# SPI_MUX.net
KiCad netlist of a schematic drawn in Altium Designer
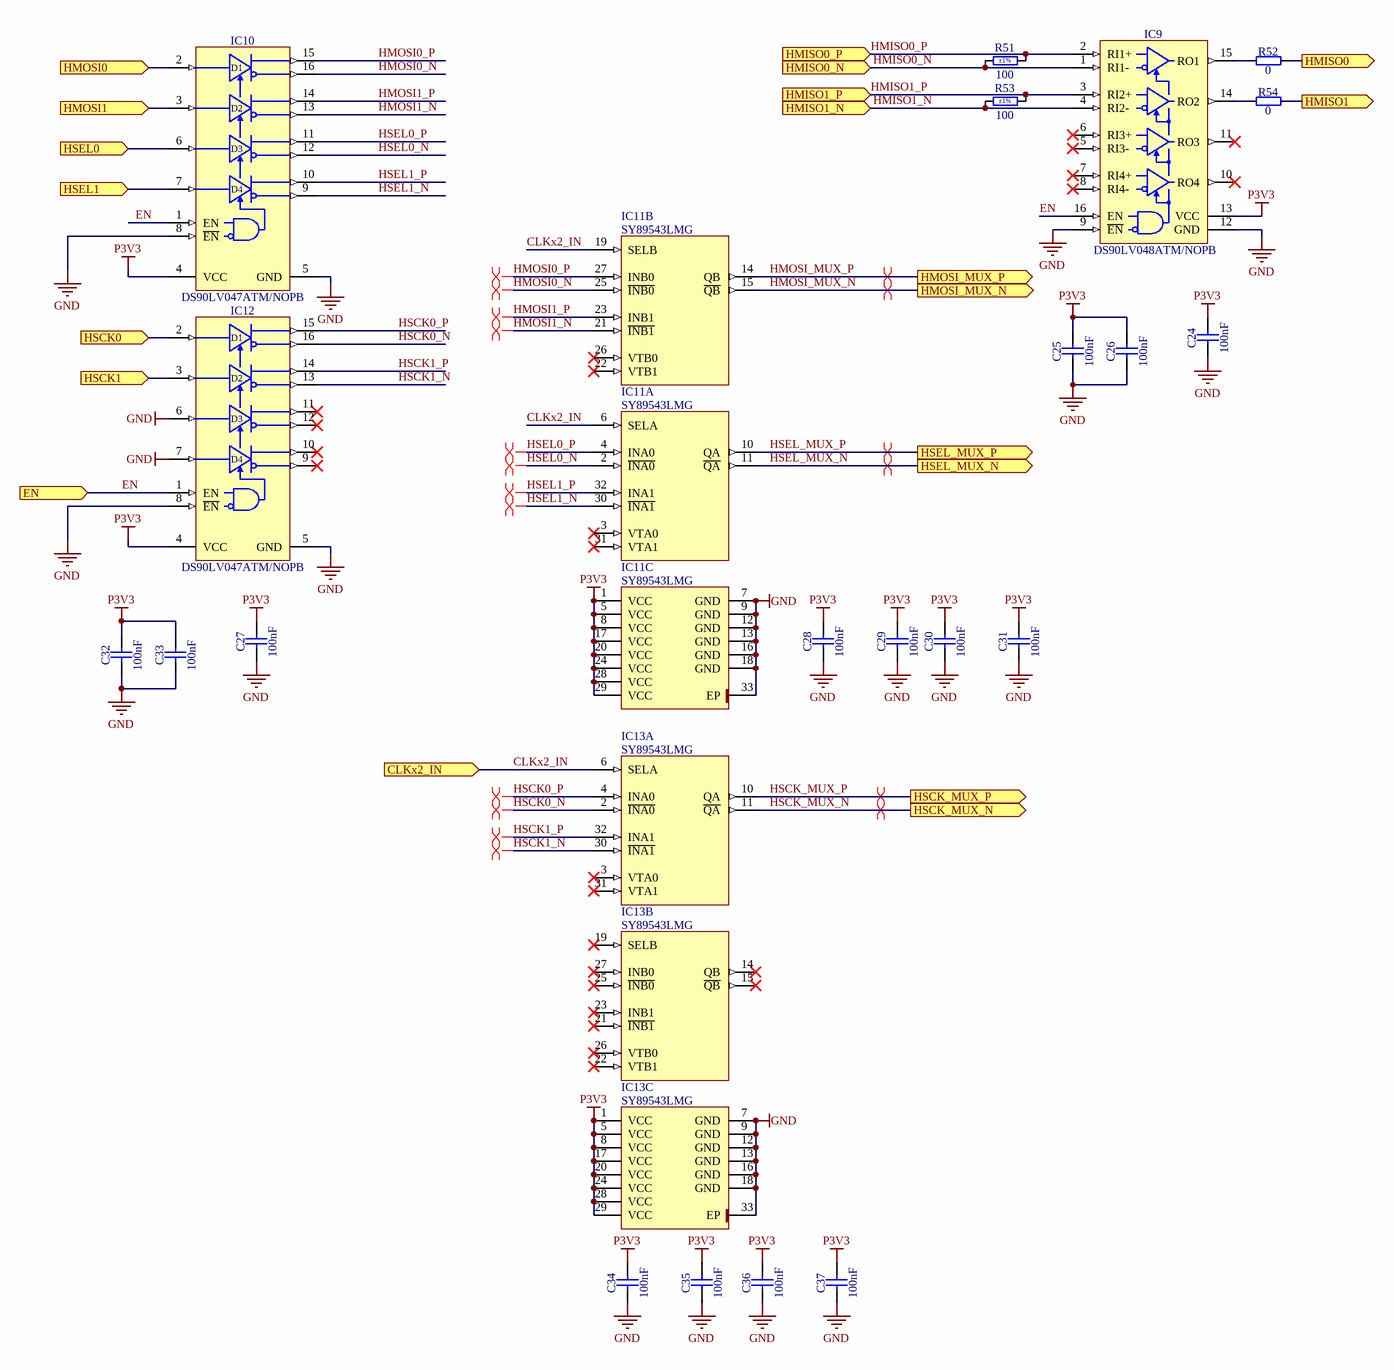
[diagram p0: SPI_MUX.SchDoc]

(export (version "E")
  (design (tool "Eeschema 10.0.6"))
  (components
    (comp (ref "C24")
      (value "100nF")
      (footprint "CAPC1005X55N")
      (description "Non-polarised capacitor")
      (fields
        (field (name "PART NUMBER") "CC0402_100NF_50V_10%_X7R")
        (field (name "VOLTAGE") "50V")
        (field (name "AUTHOR") "CERN DEM MR")
      )
      (libsource (lib "Capacitors") (part "Capacitor - non polarized"))
    )
    (comp (ref "C25")
      (value "100nF")
      (footprint "CAPC1005X55N")
      (description "Non-polarised capacitor")
      (fields
        (field (name "PART NUMBER") "CC0402_100NF_50V_10%_X7R")
        (field (name "VOLTAGE") "50V")
        (field (name "AUTHOR") "CERN DEM MR")
      )
      (libsource (lib "Capacitors") (part "Capacitor - non polarized"))
    )
    (comp (ref "C26")
      (value "100nF")
      (footprint "CAPC1005X55N")
      (description "Non-polarised capacitor")
      (fields
        (field (name "PART NUMBER") "CC0402_100NF_50V_10%_X7R")
        (field (name "VOLTAGE") "50V")
        (field (name "AUTHOR") "CERN DEM MR")
      )
      (libsource (lib "Capacitors") (part "Capacitor - non polarized"))
    )
    (comp (ref "C27")
      (value "100nF")
      (footprint "CAPC1005X55N")
      (description "Non-polarised capacitor")
      (fields
        (field (name "PART NUMBER") "CC0402_100NF_50V_10%_X7R")
        (field (name "VOLTAGE") "50V")
        (field (name "AUTHOR") "CERN DEM MR")
      )
      (libsource (lib "Capacitors") (part "Capacitor - non polarized"))
    )
    (comp (ref "C28")
      (value "100nF")
      (footprint "CAPC1005X55N")
      (description "Non-polarised capacitor")
      (fields
        (field (name "PART NUMBER") "CC0402_100NF_50V_10%_X7R")
        (field (name "VOLTAGE") "50V")
        (field (name "AUTHOR") "CERN DEM MR")
      )
      (libsource (lib "Capacitors") (part "Capacitor - non polarized"))
    )
    (comp (ref "C29")
      (value "100nF")
      (footprint "CAPC1005X55N")
      (description "Non-polarised capacitor")
      (fields
        (field (name "PART NUMBER") "CC0402_100NF_50V_10%_X7R")
        (field (name "VOLTAGE") "50V")
        (field (name "AUTHOR") "CERN DEM MR")
      )
      (libsource (lib "Capacitors") (part "Capacitor - non polarized"))
    )
    (comp (ref "C30")
      (value "100nF")
      (footprint "CAPC1005X55N")
      (description "Non-polarised capacitor")
      (fields
        (field (name "PART NUMBER") "CC0402_100NF_50V_10%_X7R")
        (field (name "VOLTAGE") "50V")
        (field (name "AUTHOR") "CERN DEM MR")
      )
      (libsource (lib "Capacitors") (part "Capacitor - non polarized"))
    )
    (comp (ref "C31")
      (value "100nF")
      (footprint "CAPC1005X55N")
      (description "Non-polarised capacitor")
      (fields
        (field (name "PART NUMBER") "CC0402_100NF_50V_10%_X7R")
        (field (name "VOLTAGE") "50V")
        (field (name "AUTHOR") "CERN DEM MR")
      )
      (libsource (lib "Capacitors") (part "Capacitor - non polarized"))
    )
    (comp (ref "C32")
      (value "100nF")
      (footprint "CAPC1005X55N")
      (description "Non-polarised capacitor")
      (fields
        (field (name "PART NUMBER") "CC0402_100NF_50V_10%_X7R")
        (field (name "VOLTAGE") "50V")
        (field (name "AUTHOR") "CERN DEM MR")
      )
      (libsource (lib "Capacitors") (part "Capacitor - non polarized"))
    )
    (comp (ref "C33")
      (value "100nF")
      (footprint "CAPC1005X55N")
      (description "Non-polarised capacitor")
      (fields
        (field (name "PART NUMBER") "CC0402_100NF_50V_10%_X7R")
        (field (name "VOLTAGE") "50V")
        (field (name "AUTHOR") "CERN DEM MR")
      )
      (libsource (lib "Capacitors") (part "Capacitor - non polarized"))
    )
    (comp (ref "C34")
      (value "100nF")
      (footprint "CAPC1005X55N")
      (description "Non-polarised capacitor")
      (fields
        (field (name "PART NUMBER") "CC0402_100NF_50V_10%_X7R")
        (field (name "VOLTAGE") "50V")
        (field (name "AUTHOR") "CERN DEM MR")
      )
      (libsource (lib "Capacitors") (part "Capacitor - non polarized"))
    )
    (comp (ref "C35")
      (value "100nF")
      (footprint "CAPC1005X55N")
      (description "Non-polarised capacitor")
      (fields
        (field (name "PART NUMBER") "CC0402_100NF_50V_10%_X7R")
        (field (name "VOLTAGE") "50V")
        (field (name "AUTHOR") "CERN DEM MR")
      )
      (libsource (lib "Capacitors") (part "Capacitor - non polarized"))
    )
    (comp (ref "C36")
      (value "100nF")
      (footprint "CAPC1005X55N")
      (description "Non-polarised capacitor")
      (fields
        (field (name "PART NUMBER") "CC0402_100NF_50V_10%_X7R")
        (field (name "VOLTAGE") "50V")
        (field (name "AUTHOR") "CERN DEM MR")
      )
      (libsource (lib "Capacitors") (part "Capacitor - non polarized"))
    )
    (comp (ref "C37")
      (value "100nF")
      (footprint "CAPC1005X55N")
      (description "Non-polarised capacitor")
      (fields
        (field (name "PART NUMBER") "CC0402_100NF_50V_10%_X7R")
        (field (name "VOLTAGE") "50V")
        (field (name "AUTHOR") "CERN DEM MR")
      )
      (libsource (lib "Capacitors") (part "Capacitor - non polarized"))
    )
    (comp (ref "IC9")
      (value "DS90LV048ATM/NOPB")
      (footprint "SOIC127P600X175-16N")
      (description "3V LVDS Quad CMOS Differential Line Receiver")
      (fields
        (field (name "MANUFACTURER") "TEXAS INSTRUMENTS")
        (field (name "MANUFACTURER PART NUMBER") "DS90LV048ATM")
        (field (name "AUTHOR") "CERN DEM JLC")
      )
      (libsource (lib "ICs And Semiconductors") (part "DS90LV048A"))
    )
    (comp (ref "IC10")
      (value "DS90LV047ATM/NOPB")
      (footprint "SOIC127P600X175-16N")
      (description "3V LVDS Quad CMOS Differential Line Driver")
      (fields
        (field (name "MANUFACTURER") "TEXAS INSTRUMENTS")
        (field (name "MANUFACTURER PART NUMBER") "DS90LV047ATM")
        (field (name "AUTHOR") "CERN DEM JLC")
      )
      (libsource (lib "ICs And Semiconductors") (part "DS90LV047A"))
    )
    (comp (ref "IC11")
      (value "SY89543LMG")
      (footprint "QFN50P500X500X90-33N-S320")
      (description "3.3V, 3.2Gbps Dual, Differential 2:1 LVDS Multiplexer With Internal Termination")
      (fields (field (name "MANUFACTURER") "MICREL") (field (name "AUTHOR") "CERN DEM JLC"))
      (libsource (lib "ICs And Semiconductors") (part "SY89543L"))
    )
    (comp (ref "IC12")
      (value "DS90LV047ATM/NOPB")
      (footprint "SOIC127P600X175-16N")
      (description "3V LVDS Quad CMOS Differential Line Driver")
      (fields
        (field (name "MANUFACTURER") "TEXAS INSTRUMENTS")
        (field (name "MANUFACTURER PART NUMBER") "DS90LV047ATM")
        (field (name "AUTHOR") "CERN DEM JLC")
      )
      (libsource (lib "ICs And Semiconductors") (part "DS90LV047A"))
    )
    (comp (ref "IC13")
      (value "SY89543LMG")
      (footprint "QFN50P500X500X90-33N-S320")
      (description "3.3V, 3.2Gbps Dual, Differential 2:1 LVDS Multiplexer With Internal Termination")
      (fields (field (name "MANUFACTURER") "MICREL") (field (name "AUTHOR") "CERN DEM JLC"))
      (libsource (lib "ICs And Semiconductors") (part "SY89543L"))
    )
    (comp (ref "R51")
      (value "100")
      (footprint "RESC1005X40N")
      (description "Resistor - 1%")
      (fields
        (field (name "TOLERANCE") "±1%")
        (field (name "PART NUMBER") "R0402_100R_1%_0.0625W_100PPM")
        (field (name "POWER") "0.0625W")
        (field (name "AUTHOR") "CERN DEM JLC")
      )
      (libsource (lib "Resistors") (part "Resistor - 1%"))
    )
    (comp (ref "R52")
      (value "0")
      (footprint "RESC1005X40N")
      (description "Resistor")
      (fields
        (field (name "PART NUMBER") "R0402_0R_JUMPER")
        (field (name "MANUFACTURER") "GENERIC")
        (field (name "AUTHOR") "CERN DEM JLC")
      )
      (libsource (lib "Resistors") (part "Resistor"))
    )
    (comp (ref "R53")
      (value "100")
      (footprint "RESC1005X40N")
      (description "Resistor - 1%")
      (fields
        (field (name "TOLERANCE") "±1%")
        (field (name "PART NUMBER") "R0402_100R_1%_0.0625W_100PPM")
        (field (name "POWER") "0.0625W")
        (field (name "AUTHOR") "CERN DEM JLC")
      )
      (libsource (lib "Resistors") (part "Resistor - 1%"))
    )
    (comp (ref "R54")
      (value "0")
      (footprint "RESC1005X40N")
      (description "Resistor")
      (fields
        (field (name "PART NUMBER") "R0402_0R_JUMPER")
        (field (name "MANUFACTURER") "GENERIC")
        (field (name "AUTHOR") "CERN DEM JLC")
      )
      (libsource (lib "Resistors") (part "Resistor"))
    )
  )
  (nets
    (net (code "1") (name "/CLKx2_IN") (class "Default")
      (node (ref "IC11") (pin "19") (pinfunction "SELB_19") (pintype "input"))
      (node (ref "IC11") (pin "6") (pinfunction "SELA_6") (pintype "input"))
      (node (ref "IC13") (pin "6") (pinfunction "SELA_6") (pintype "input"))
    )
    (net (code "2") (name "/EN") (class "Default")
      (node (ref "IC10") (pin "1") (pinfunction "EN_1") (pintype "input"))
      (node (ref "IC12") (pin "1") (pinfunction "EN_1") (pintype "input"))
      (node (ref "IC9") (pin "16") (pinfunction "EN_16") (pintype "input"))
    )
    (net (code "3") (name "/HMISO0") (class "Default")
      (node (ref "R52") (pin "2") (pinfunction "2_2") (pintype "passive"))
    )
    (net (code "4") (name "/HMISO0_N") (class "Default")
      (node (ref "IC9") (pin "1") (pinfunction "RI1-_1") (pintype "input"))
      (node (ref "R51") (pin "1") (pinfunction "1_1") (pintype "passive"))
    )
    (net (code "5") (name "/HMISO0_P") (class "Default")
      (node (ref "IC9") (pin "2") (pinfunction "RI1+_2") (pintype "input"))
      (node (ref "R51") (pin "2") (pinfunction "2_2") (pintype "passive"))
    )
    (net (code "6") (name "/HMISO1") (class "Default")
      (node (ref "R54") (pin "2") (pinfunction "2_2") (pintype "passive"))
    )
    (net (code "7") (name "/HMISO1_N") (class "Default")
      (node (ref "IC9") (pin "4") (pinfunction "RI2-_4") (pintype "input"))
      (node (ref "R53") (pin "1") (pinfunction "1_1") (pintype "passive"))
    )
    (net (code "8") (name "/HMISO1_P") (class "Default")
      (node (ref "IC9") (pin "3") (pinfunction "RI2+_3") (pintype "input"))
      (node (ref "R53") (pin "2") (pinfunction "2_2") (pintype "passive"))
    )
    (net (code "9") (name "/HMOSI0") (class "Default")
      (node (ref "IC10") (pin "2") (pinfunction "DIN1_2") (pintype "input"))
    )
    (net (code "10") (name "/HMOSI0_N") (class "Default")
      (node (ref "IC10") (pin "16") (pinfunction "DOUT1-_16") (pintype "output"))
      (node (ref "IC11") (pin "25") (pinfunction "~{INB0}_25") (pintype "input"))
    )
    (net (code "11") (name "/HMOSI0_P") (class "Default")
      (node (ref "IC10") (pin "15") (pinfunction "DOUT1+_15") (pintype "output"))
      (node (ref "IC11") (pin "27") (pinfunction "INB0_27") (pintype "input"))
    )
    (net (code "12") (name "/HMOSI1") (class "Default")
      (node (ref "IC10") (pin "3") (pinfunction "DIN2_3") (pintype "input"))
    )
    (net (code "13") (name "/HMOSI1_N") (class "Default")
      (node (ref "IC10") (pin "13") (pinfunction "DOUT2-_13") (pintype "output"))
      (node (ref "IC11") (pin "21") (pinfunction "~{INB1}_21") (pintype "input"))
    )
    (net (code "14") (name "/HMOSI1_P") (class "Default")
      (node (ref "IC10") (pin "14") (pinfunction "DOUT2+_14") (pintype "output"))
      (node (ref "IC11") (pin "23") (pinfunction "INB1_23") (pintype "input"))
    )
    (net (code "15") (name "/HMOSI_MUX_N") (class "Default")
      (node (ref "IC11") (pin "15") (pinfunction "~{QB}_15") (pintype "output"))
    )
    (net (code "16") (name "/HMOSI_MUX_P") (class "Default")
      (node (ref "IC11") (pin "14") (pinfunction "QB_14") (pintype "output"))
    )
    (net (code "17") (name "/HSCK0") (class "Default")
      (node (ref "IC12") (pin "2") (pinfunction "DIN1_2") (pintype "input"))
    )
    (net (code "18") (name "/HSCK0_N") (class "Default")
      (node (ref "IC12") (pin "16") (pinfunction "DOUT1-_16") (pintype "output"))
      (node (ref "IC13") (pin "2") (pinfunction "~{INA0}_2") (pintype "input"))
    )
    (net (code "19") (name "/HSCK0_P") (class "Default")
      (node (ref "IC12") (pin "15") (pinfunction "DOUT1+_15") (pintype "output"))
      (node (ref "IC13") (pin "4") (pinfunction "INA0_4") (pintype "input"))
    )
    (net (code "20") (name "/HSCK1") (class "Default")
      (node (ref "IC12") (pin "3") (pinfunction "DIN2_3") (pintype "input"))
    )
    (net (code "21") (name "/HSCK1_N") (class "Default")
      (node (ref "IC12") (pin "13") (pinfunction "DOUT2-_13") (pintype "output"))
      (node (ref "IC13") (pin "30") (pinfunction "~{INA1}_30") (pintype "input"))
    )
    (net (code "22") (name "/HSCK1_P") (class "Default")
      (node (ref "IC12") (pin "14") (pinfunction "DOUT2+_14") (pintype "output"))
      (node (ref "IC13") (pin "32") (pinfunction "INA1_32") (pintype "input"))
    )
    (net (code "23") (name "/HSCK_MUX_N") (class "Default")
      (node (ref "IC13") (pin "11") (pinfunction "~{QA}_11") (pintype "output"))
    )
    (net (code "24") (name "/HSCK_MUX_P") (class "Default")
      (node (ref "IC13") (pin "10") (pinfunction "QA_10") (pintype "output"))
    )
    (net (code "25") (name "/HSEL0") (class "Default")
      (node (ref "IC10") (pin "6") (pinfunction "DIN3_6") (pintype "input"))
    )
    (net (code "26") (name "/HSEL0_N") (class "Default")
      (node (ref "IC10") (pin "12") (pinfunction "DOUT3-_12") (pintype "output"))
      (node (ref "IC11") (pin "2") (pinfunction "~{INA0}_2") (pintype "input"))
    )
    (net (code "27") (name "/HSEL0_P") (class "Default")
      (node (ref "IC10") (pin "11") (pinfunction "DOUT3+_11") (pintype "output"))
      (node (ref "IC11") (pin "4") (pinfunction "INA0_4") (pintype "input"))
    )
    (net (code "28") (name "/HSEL1") (class "Default")
      (node (ref "IC10") (pin "7") (pinfunction "DIN4_7") (pintype "input"))
    )
    (net (code "29") (name "/HSEL1_N") (class "Default")
      (node (ref "IC10") (pin "9") (pinfunction "DOUT4-_9") (pintype "output"))
      (node (ref "IC11") (pin "30") (pinfunction "~{INA1}_30") (pintype "input"))
    )
    (net (code "30") (name "/HSEL1_P") (class "Default")
      (node (ref "IC10") (pin "10") (pinfunction "DOUT4+_10") (pintype "output"))
      (node (ref "IC11") (pin "32") (pinfunction "INA1_32") (pintype "input"))
    )
    (net (code "31") (name "/HSEL_MUX_N") (class "Default")
      (node (ref "IC11") (pin "11") (pinfunction "~{QA}_11") (pintype "output"))
    )
    (net (code "32") (name "/HSEL_MUX_P") (class "Default")
      (node (ref "IC11") (pin "10") (pinfunction "QA_10") (pintype "output"))
    )
    (net (code "33") (name "GND") (class "Default")
      (node (ref "C24") (pin "1") (pinfunction "1_1") (pintype "passive"))
      (node (ref "C25") (pin "1") (pinfunction "1_1") (pintype "passive"))
      (node (ref "C26") (pin "1") (pinfunction "1_1") (pintype "passive"))
      (node (ref "C27") (pin "1") (pinfunction "1_1") (pintype "passive"))
      (node (ref "C28") (pin "1") (pinfunction "1_1") (pintype "passive"))
      (node (ref "C29") (pin "1") (pinfunction "1_1") (pintype "passive"))
      (node (ref "C30") (pin "1") (pinfunction "1_1") (pintype "passive"))
      (node (ref "C31") (pin "1") (pinfunction "1_1") (pintype "passive"))
      (node (ref "C32") (pin "1") (pinfunction "1_1") (pintype "passive"))
      (node (ref "C33") (pin "1") (pinfunction "1_1") (pintype "passive"))
      (node (ref "C34") (pin "1") (pinfunction "1_1") (pintype "passive"))
      (node (ref "C35") (pin "1") (pinfunction "1_1") (pintype "passive"))
      (node (ref "C36") (pin "1") (pinfunction "1_1") (pintype "passive"))
      (node (ref "C37") (pin "1") (pinfunction "1_1") (pintype "passive"))
      (node (ref "IC10") (pin "5") (pinfunction "GND_5") (pintype "power_in"))
      (node (ref "IC10") (pin "8") (pinfunction "~{EN}_8") (pintype "input"))
      (node (ref "IC11") (pin "12") (pinfunction "GND_12") (pintype "power_in"))
      (node (ref "IC11") (pin "13") (pinfunction "GND_13") (pintype "power_in"))
      (node (ref "IC11") (pin "16") (pinfunction "GND_16") (pintype "power_in"))
      (node (ref "IC11") (pin "18") (pinfunction "GND_18") (pintype "power_in"))
      (node (ref "IC11") (pin "33") (pinfunction "EP_33") (pintype "power_in"))
      (node (ref "IC11") (pin "7") (pinfunction "GND_7") (pintype "power_in"))
      (node (ref "IC11") (pin "9") (pinfunction "GND_9") (pintype "power_in"))
      (node (ref "IC12") (pin "5") (pinfunction "GND_5") (pintype "power_in"))
      (node (ref "IC12") (pin "6") (pinfunction "DIN3_6") (pintype "input"))
      (node (ref "IC12") (pin "7") (pinfunction "DIN4_7") (pintype "input"))
      (node (ref "IC12") (pin "8") (pinfunction "~{EN}_8") (pintype "input"))
      (node (ref "IC13") (pin "12") (pinfunction "GND_12") (pintype "power_in"))
      (node (ref "IC13") (pin "13") (pinfunction "GND_13") (pintype "power_in"))
      (node (ref "IC13") (pin "16") (pinfunction "GND_16") (pintype "power_in"))
      (node (ref "IC13") (pin "18") (pinfunction "GND_18") (pintype "power_in"))
      (node (ref "IC13") (pin "33") (pinfunction "EP_33") (pintype "power_in"))
      (node (ref "IC13") (pin "7") (pinfunction "GND_7") (pintype "power_in"))
      (node (ref "IC13") (pin "9") (pinfunction "GND_9") (pintype "power_in"))
      (node (ref "IC9") (pin "12") (pinfunction "GND_12") (pintype "power_in"))
      (node (ref "IC9") (pin "9") (pinfunction "~{EN}_9") (pintype "input"))
    )
    (net (code "34") (name "Net-(IC9-RO1)") (class "Default")
      (node (ref "IC9") (pin "15") (pinfunction "RO1_15") (pintype "output"))
      (node (ref "R52") (pin "1") (pinfunction "1_1") (pintype "passive"))
    )
    (net (code "35") (name "Net-(IC9-RO2)") (class "Default")
      (node (ref "IC9") (pin "14") (pinfunction "RO2_14") (pintype "output"))
      (node (ref "R54") (pin "1") (pinfunction "1_1") (pintype "passive"))
    )
    (net (code "36") (name "P3V3") (class "Default")
      (node (ref "C24") (pin "2") (pinfunction "2_2") (pintype "passive"))
      (node (ref "C25") (pin "2") (pinfunction "2_2") (pintype "passive"))
      (node (ref "C26") (pin "2") (pinfunction "2_2") (pintype "passive"))
      (node (ref "C27") (pin "2") (pinfunction "2_2") (pintype "passive"))
      (node (ref "C28") (pin "2") (pinfunction "2_2") (pintype "passive"))
      (node (ref "C29") (pin "2") (pinfunction "2_2") (pintype "passive"))
      (node (ref "C30") (pin "2") (pinfunction "2_2") (pintype "passive"))
      (node (ref "C31") (pin "2") (pinfunction "2_2") (pintype "passive"))
      (node (ref "C32") (pin "2") (pinfunction "2_2") (pintype "passive"))
      (node (ref "C33") (pin "2") (pinfunction "2_2") (pintype "passive"))
      (node (ref "C34") (pin "2") (pinfunction "2_2") (pintype "passive"))
      (node (ref "C35") (pin "2") (pinfunction "2_2") (pintype "passive"))
      (node (ref "C36") (pin "2") (pinfunction "2_2") (pintype "passive"))
      (node (ref "C37") (pin "2") (pinfunction "2_2") (pintype "passive"))
      (node (ref "IC10") (pin "4") (pinfunction "VCC_4") (pintype "power_in"))
      (node (ref "IC11") (pin "1") (pinfunction "VCC_1") (pintype "power_in"))
      (node (ref "IC11") (pin "17") (pinfunction "VCC_17") (pintype "power_in"))
      (node (ref "IC11") (pin "20") (pinfunction "VCC_20") (pintype "power_in"))
      (node (ref "IC11") (pin "24") (pinfunction "VCC_24") (pintype "power_in"))
      (node (ref "IC11") (pin "28") (pinfunction "VCC_28") (pintype "power_in"))
      (node (ref "IC11") (pin "29") (pinfunction "VCC_29") (pintype "power_in"))
      (node (ref "IC11") (pin "5") (pinfunction "VCC_5") (pintype "power_in"))
      (node (ref "IC11") (pin "8") (pinfunction "VCC_8") (pintype "power_in"))
      (node (ref "IC12") (pin "4") (pinfunction "VCC_4") (pintype "power_in"))
      (node (ref "IC13") (pin "1") (pinfunction "VCC_1") (pintype "power_in"))
      (node (ref "IC13") (pin "17") (pinfunction "VCC_17") (pintype "power_in"))
      (node (ref "IC13") (pin "20") (pinfunction "VCC_20") (pintype "power_in"))
      (node (ref "IC13") (pin "24") (pinfunction "VCC_24") (pintype "power_in"))
      (node (ref "IC13") (pin "28") (pinfunction "VCC_28") (pintype "power_in"))
      (node (ref "IC13") (pin "29") (pinfunction "VCC_29") (pintype "power_in"))
      (node (ref "IC13") (pin "5") (pinfunction "VCC_5") (pintype "power_in"))
      (node (ref "IC13") (pin "8") (pinfunction "VCC_8") (pintype "power_in"))
      (node (ref "IC9") (pin "13") (pinfunction "VCC_13") (pintype "power_in"))
    )
    (net (code "37") (name "unconnected-(IC9-RI3+-Pad6)") (class "Default")
      (node (ref "IC9") (pin "6") (pinfunction "RI3+_6") (pintype "input+no_connect"))
    )
    (net (code "38") (name "unconnected-(IC9-RI3--Pad5)") (class "Default")
      (node (ref "IC9") (pin "5") (pinfunction "RI3-_5") (pintype "input+no_connect"))
    )
    (net (code "39") (name "unconnected-(IC9-RI4+-Pad7)") (class "Default")
      (node (ref "IC9") (pin "7") (pinfunction "RI4+_7") (pintype "input+no_connect"))
    )
    (net (code "40") (name "unconnected-(IC9-RI4--Pad8)") (class "Default")
      (node (ref "IC9") (pin "8") (pinfunction "RI4-_8") (pintype "input+no_connect"))
    )
    (net (code "41") (name "unconnected-(IC9-RO3-Pad11)") (class "Default")
      (node (ref "IC9") (pin "11") (pinfunction "RO3_11") (pintype "output+no_connect"))
    )
    (net (code "42") (name "unconnected-(IC9-RO4-Pad10)") (class "Default")
      (node (ref "IC9") (pin "10") (pinfunction "RO4_10") (pintype "output+no_connect"))
    )
    (net (code "43") (name "unconnected-(IC11A-VTA0-Pad3)") (class "Default")
      (node (ref "IC11") (pin "3") (pinfunction "VTA0_3") (pintype "input+no_connect"))
    )
    (net (code "44") (name "unconnected-(IC11A-VTA1-Pad31)") (class "Default")
      (node (ref "IC11") (pin "31") (pinfunction "VTA1_31") (pintype "input+no_connect"))
    )
    (net (code "45") (name "unconnected-(IC11B-VTB0-Pad26)") (class "Default")
      (node (ref "IC11") (pin "26") (pinfunction "VTB0_26") (pintype "input+no_connect"))
    )
    (net (code "46") (name "unconnected-(IC11B-VTB1-Pad22)") (class "Default")
      (node (ref "IC11") (pin "22") (pinfunction "VTB1_22") (pintype "input+no_connect"))
    )
    (net (code "47") (name "unconnected-(IC12-DOUT3+-Pad11)") (class "Default")
      (node (ref "IC12") (pin "11") (pinfunction "DOUT3+_11") (pintype "output+no_connect"))
    )
    (net (code "48") (name "unconnected-(IC12-DOUT3--Pad12)") (class "Default")
      (node (ref "IC12") (pin "12") (pinfunction "DOUT3-_12") (pintype "output+no_connect"))
    )
    (net (code "49") (name "unconnected-(IC12-DOUT4+-Pad10)") (class "Default")
      (node (ref "IC12") (pin "10") (pinfunction "DOUT4+_10") (pintype "output+no_connect"))
    )
    (net (code "50") (name "unconnected-(IC12-DOUT4--Pad9)") (class "Default")
      (node (ref "IC12") (pin "9") (pinfunction "DOUT4-_9") (pintype "output+no_connect"))
    )
    (net (code "51") (name "unconnected-(IC13A-VTA0-Pad3)") (class "Default")
      (node (ref "IC13") (pin "3") (pinfunction "VTA0_3") (pintype "input+no_connect"))
    )
    (net (code "52") (name "unconnected-(IC13A-VTA1-Pad31)") (class "Default")
      (node (ref "IC13") (pin "31") (pinfunction "VTA1_31") (pintype "input+no_connect"))
    )
    (net (code "53") (name "unconnected-(IC13B-INB0-Pad27)") (class "Default")
      (node (ref "IC13") (pin "27") (pinfunction "INB0_27") (pintype "input+no_connect"))
    )
    (net (code "54") (name "unconnected-(IC13B-INB1-Pad23)") (class "Default")
      (node (ref "IC13") (pin "23") (pinfunction "INB1_23") (pintype "input+no_connect"))
    )
    (net (code "55") (name "unconnected-(IC13B-QB-Pad14)") (class "Default")
      (node (ref "IC13") (pin "14") (pinfunction "QB_14") (pintype "output+no_connect"))
    )
    (net (code "56") (name "unconnected-(IC13B-SELB-Pad19)") (class "Default")
      (node (ref "IC13") (pin "19") (pinfunction "SELB_19") (pintype "input+no_connect"))
    )
    (net (code "57") (name "unconnected-(IC13B-VTB0-Pad26)") (class "Default")
      (node (ref "IC13") (pin "26") (pinfunction "VTB0_26") (pintype "input+no_connect"))
    )
    (net (code "58") (name "unconnected-(IC13B-VTB1-Pad22)") (class "Default")
      (node (ref "IC13") (pin "22") (pinfunction "VTB1_22") (pintype "input+no_connect"))
    )
    (net (code "59") (name "unconnected-(IC13B-~{INB0}-Pad25)") (class "Default")
      (node (ref "IC13") (pin "25") (pinfunction "~{INB0}_25") (pintype "input+no_connect"))
    )
    (net (code "60") (name "unconnected-(IC13B-~{INB1}-Pad21)") (class "Default")
      (node (ref "IC13") (pin "21") (pinfunction "~{INB1}_21") (pintype "input+no_connect"))
    )
    (net (code "61") (name "unconnected-(IC13B-~{QB}-Pad15)") (class "Default")
      (node (ref "IC13") (pin "15") (pinfunction "~{QB}_15") (pintype "output+no_connect"))
    )
  )
)
